# 01_-_PWR_0V9_PWR_SEQ.net
KiCad netlist of a schematic drawn in Altium Designer
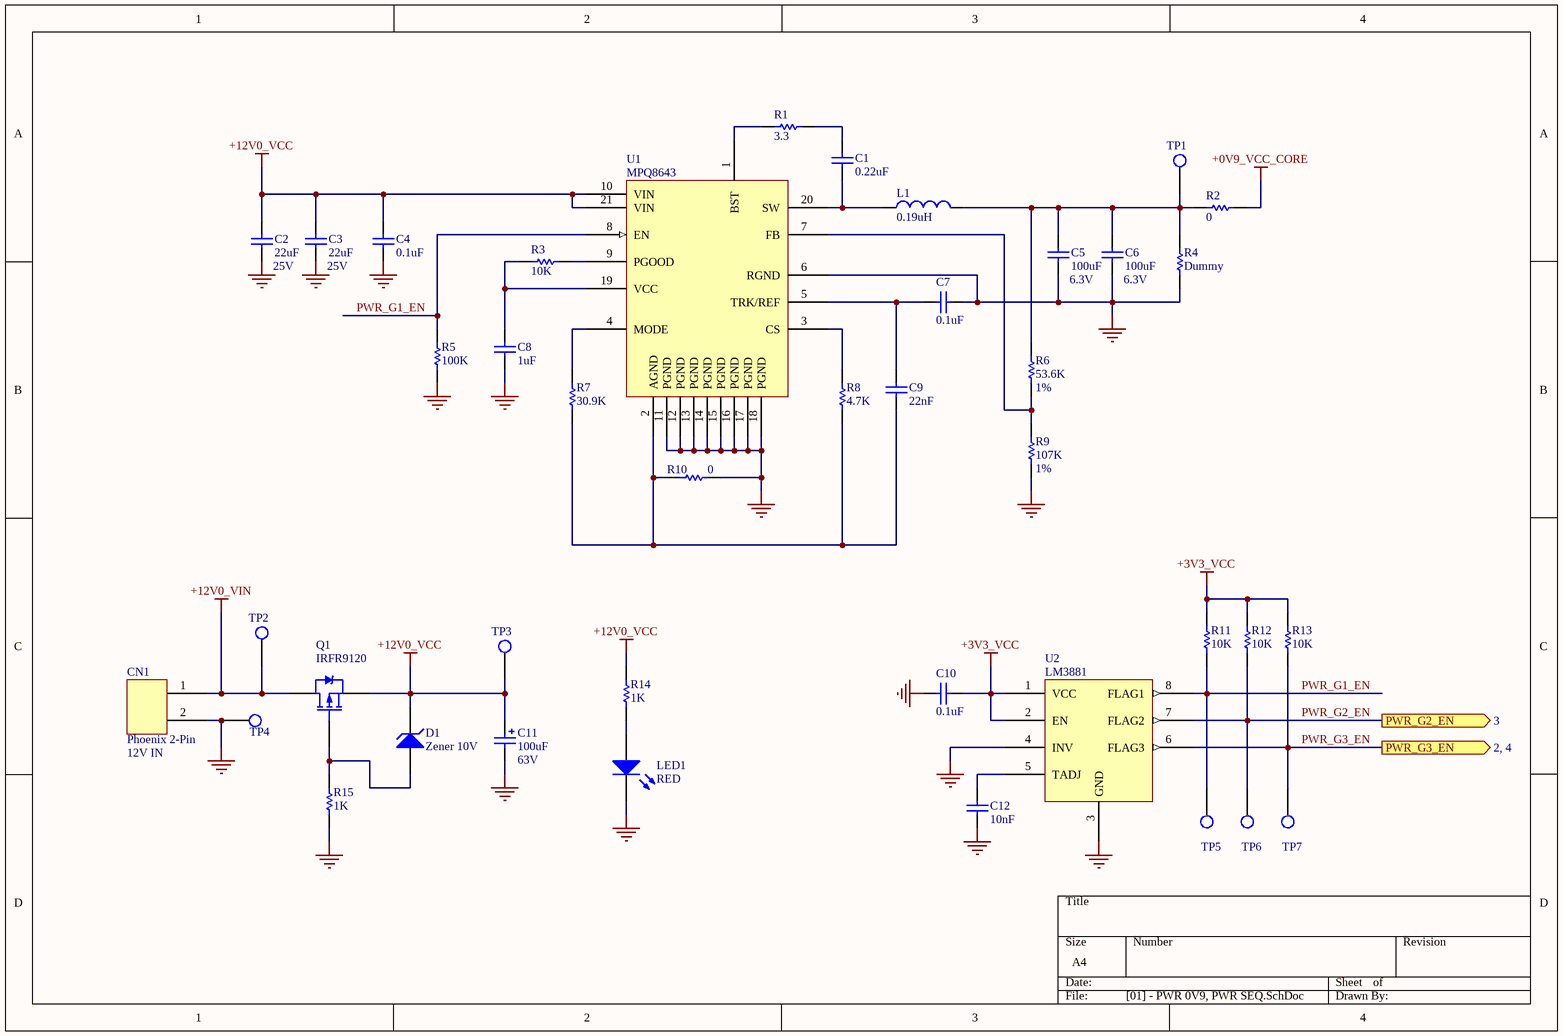
[diagram p0: [01] - PWR 0V9, PWR SEQ.SchDoc]

(export (version "E")
  (design (tool "Eeschema 10.0.6"))
  (components
    (comp (ref "C1")
      (value "0.22uF")
      (footprint "0402_C")
      (description "Non-Pol SMD Capacitor")
      (libsource (lib "Passive Components") (part "Cap SMD"))
    )
    (comp (ref "C2")
      (value "22uF")
      (footprint "1210_C")
      (description "Non-Pol SMD Capacitor")
      (fields (field (name "RATED_VOLTAGE") "25V") (field (name "MANUFACTURER PART NUM") "GRM32ER71E226KE15"))
      (libsource (lib "Passive Components") (part "Cap SMD"))
    )
    (comp (ref "C3")
      (value "22uF")
      (footprint "1210_C")
      (description "Non-Pol SMD Capacitor")
      (fields (field (name "RATED_VOLTAGE") "25V") (field (name "MANUFACTURER PART NUM") "GRM32ER71E226KE15"))
      (libsource (lib "Passive Components") (part "Cap SMD"))
    )
    (comp (ref "C4")
      (value "0.1uF")
      (footprint "0402_C")
      (description "Non-Pol SMD Capacitor")
      (libsource (lib "Passive Components") (part "Cap SMD"))
    )
    (comp (ref "C5")
      (value "100uF")
      (footprint "1210_C")
      (description "Non-Pol SMD Capacitor")
      (fields
        (field (name "RATED_VOLTAGE") "6.3V")
        (field (name "MANUFACTURER PART NUM") "GRM32EC70J107ME15")
      )
      (libsource (lib "Passive Components") (part "Cap SMD"))
    )
    (comp (ref "C6")
      (value "100uF")
      (footprint "1210_C")
      (description "Non-Pol SMD Capacitor")
      (fields
        (field (name "RATED_VOLTAGE") "6.3V")
        (field (name "MANUFACTURER PART NUM") "GRM32EC70J107ME15")
      )
      (libsource (lib "Passive Components") (part "Cap SMD"))
    )
    (comp (ref "C7")
      (value "0.1uF")
      (footprint "0402_C")
      (description "Non-Pol SMD Capacitor")
      (libsource (lib "Passive Components") (part "Cap SMD"))
    )
    (comp (ref "C8")
      (value "1uF")
      (footprint "0402_C")
      (description "Non-Pol SMD Capacitor")
      (libsource (lib "Passive Components") (part "Cap SMD"))
    )
    (comp (ref "C9")
      (value "22nF")
      (footprint "0402_C")
      (description "Non-Pol SMD Capacitor")
      (libsource (lib "Passive Components") (part "Cap SMD"))
    )
    (comp (ref "C10")
      (value "0.1uF")
      (footprint "0402_C")
      (description "Non-Pol SMD Capacitor")
      (libsource (lib "Passive Components") (part "Cap SMD"))
    )
    (comp (ref "C11")
      (value "100uF")
      (footprint "G_PANASONIC")
      (description "Aluminium Electrolytic Capacitor")
      (fields (field (name "RATED_VOLTAGE") "63V") (field (name "MANUFACTURER PART NUM") "EEE-TG1J101UP"))
      (libsource (lib "Passive Components") (part "Cap Aluminium Electrolytic"))
    )
    (comp (ref "C12")
      (value "10nF")
      (footprint "0402_C")
      (description "Non-Pol SMD Capacitor")
      (libsource (lib "Passive Components") (part "Cap SMD"))
    )
    (comp (ref "CN1")
      (value "Phoenix 2-Pin")
      (footprint "PHOENIX_2PIN_RIGHT_200mil")
      (description "2-Pin Phoenix Terminal")
      (libsource (lib "Connectors") (part "Phoenix 2 pin"))
    )
    (comp (ref "D1")
      (value "Zener 10V")
      (footprint "SOD-123")
      (description "Zener Diode")
      (fields (field (name "MANUFACTURER PART NUM") "BZT52C10-7-F"))
      (libsource (lib "Common Components") (part "Diode Zener"))
    )
    (comp (ref "L1")
      (value "0.19uH")
      (footprint "IHLP-4040")
      (description "Inductor SMD")
      (fields (field (name "MANUFACTURER PART NUM") "IHLP4040DZERR19M11"))
      (libsource (lib "Passive Components") (part "Inductor"))
    )
    (comp (ref "LED1")
      (value "RED")
      (footprint "LED_0805")
      (description "Typical LED")
      (libsource (lib "Common Components") (part "LED"))
    )
    (comp (ref "Q1")
      (value "IRFR9120")
      (footprint "TO-252")
      (description "P-Channel Mosfet")
      (fields (field (name "MANUFACTURER PART NUM") "IRFR9120PBF"))
      (libsource (lib "Common Components") (part "MOSFET P-CH"))
    )
    (comp (ref "R1")
      (value "3.3")
      (footprint "0402_R")
      (description "SMD Resistor")
      (fields (field (name "TOLERANCE") "5%"))
      (libsource (lib "Passive Components") (part "Res SMD"))
    )
    (comp (ref "R2")
      (value "0")
      (footprint "1210_R")
      (description "SMD Resistor")
      (fields (field (name "TOLERANCE") "5%"))
      (libsource (lib "Passive Components") (part "Res SMD"))
    )
    (comp (ref "R3")
      (value "10K")
      (footprint "0402_R")
      (description "SMD Resistor")
      (fields (field (name "TOLERANCE") "5%"))
      (libsource (lib "Passive Components") (part "Res SMD"))
    )
    (comp (ref "R4")
      (value "Dummy")
      (footprint "1210_R")
      (description "SMD Resistor")
      (fields (field (name "TOLERANCE") "5%"))
      (libsource (lib "Passive Components") (part "Res SMD"))
    )
    (comp (ref "R5")
      (value "100K")
      (footprint "0402_R")
      (description "SMD Resistor")
      (fields (field (name "TOLERANCE") "5%"))
      (libsource (lib "Passive Components") (part "Res SMD"))
    )
    (comp (ref "R6")
      (value "53.6K")
      (footprint "0402_R")
      (description "SMD Resistor")
      (fields (field (name "TOLERANCE") "1%"))
      (libsource (lib "Passive Components") (part "Res SMD"))
    )
    (comp (ref "R7")
      (value "30.9K")
      (footprint "0402_R")
      (description "SMD Resistor")
      (fields (field (name "TOLERANCE") "5%"))
      (libsource (lib "Passive Components") (part "Res SMD"))
    )
    (comp (ref "R8")
      (value "4.7K")
      (footprint "0402_R")
      (description "SMD Resistor")
      (fields (field (name "TOLERANCE") "5%"))
      (libsource (lib "Passive Components") (part "Res SMD"))
    )
    (comp (ref "R9")
      (value "107K")
      (footprint "0402_R")
      (description "SMD Resistor")
      (fields (field (name "TOLERANCE") "1%"))
      (libsource (lib "Passive Components") (part "Res SMD"))
    )
    (comp (ref "R10")
      (value "0")
      (footprint "0402_R")
      (description "SMD Resistor")
      (fields (field (name "TOLERANCE") "5%"))
      (libsource (lib "Passive Components") (part "Res SMD"))
    )
    (comp (ref "R11")
      (value "10K")
      (footprint "0402_R")
      (description "SMD Resistor")
      (fields (field (name "TOLERANCE") "5%"))
      (libsource (lib "Passive Components") (part "Res SMD"))
    )
    (comp (ref "R12")
      (value "10K")
      (footprint "0402_R")
      (description "SMD Resistor")
      (fields (field (name "TOLERANCE") "5%"))
      (libsource (lib "Passive Components") (part "Res SMD"))
    )
    (comp (ref "R13")
      (value "10K")
      (footprint "0402_R")
      (description "SMD Resistor")
      (fields (field (name "TOLERANCE") "5%"))
      (libsource (lib "Passive Components") (part "Res SMD"))
    )
    (comp (ref "R14")
      (value "1K")
      (footprint "0805_R")
      (description "SMD Resistor")
      (fields (field (name "TOLERANCE") "5%"))
      (libsource (lib "Passive Components") (part "Res SMD"))
    )
    (comp (ref "R15")
      (value "1K")
      (footprint "0805_R")
      (description "SMD Resistor")
      (fields (field (name "TOLERANCE") "5%"))
      (libsource (lib "Passive Components") (part "Res SMD"))
    )
    (comp (ref "TP1")
      (value "Test Point")
      (footprint "PIN_1.5mm")
      (description "Test Point Footprint")
      (libsource (lib "Passive Components") (part "Test Point"))
    )
    (comp (ref "TP2")
      (value "Test Point")
      (footprint "PIN_1.5mm")
      (description "Test Point Footprint")
      (libsource (lib "Passive Components") (part "Test Point"))
    )
    (comp (ref "TP3")
      (value "Test Point")
      (footprint "PIN_1.5mm")
      (description "Test Point Footprint")
      (libsource (lib "Passive Components") (part "Test Point"))
    )
    (comp (ref "TP4")
      (value "Test Point")
      (footprint "PIN_1.5mm")
      (description "Test Point Footprint")
      (libsource (lib "Passive Components") (part "Test Point"))
    )
    (comp (ref "TP5")
      (value "Test Point")
      (footprint "PIN_1mm")
      (description "Test Point Footprint")
      (libsource (lib "Passive Components") (part "Test Point"))
    )
    (comp (ref "TP6")
      (value "Test Point")
      (footprint "PIN_1mm")
      (description "Test Point Footprint")
      (libsource (lib "Passive Components") (part "Test Point"))
    )
    (comp (ref "TP7")
      (value "Test Point")
      (footprint "PIN_1mm")
      (description "Test Point Footprint")
      (libsource (lib "Passive Components") (part "Test Point"))
    )
    (comp (ref "U1")
      (value "MPQ8643")
      (description "16V, 20A, Configurable-Frequency, Synchronous Step-Down Converter")
      (fields (field (name "MANUFACTURER PART NUM") "MPQ8643GLE-P"))
      (libsource (lib "Project_schlib") (part "MPQ8643"))
    )
    (comp (ref "U2")
      (value "LM3881")
      (description "Simple Power Sequencer With Adjustable Timing")
      (libsource (lib "Project_schlib") (part "LM3881"))
    )
  )
  (nets
    (net (code "1") (name "+0V9_VCC_CORE") (class "Default")
      (node (ref "R2") (pin "2") (pinfunction "2_2") (pintype "passive"))
    )
    (net (code "2") (name "+3V3_VCC") (class "Default")
      (node (ref "C10") (pin "1") (pinfunction "1_1") (pintype "passive"))
      (node (ref "R11") (pin "2") (pinfunction "2_2") (pintype "passive"))
      (node (ref "R12") (pin "2") (pinfunction "2_2") (pintype "passive"))
      (node (ref "R13") (pin "2") (pinfunction "2_2") (pintype "passive"))
      (node (ref "U2") (pin "1") (pinfunction "VCC_1") (pintype "power_in"))
      (node (ref "U2") (pin "2") (pinfunction "EN_2") (pintype "passive"))
    )
    (net (code "3") (name "+12V0_VCC") (class "Default")
      (node (ref "C11") (pin "1") (pinfunction "1_1") (pintype "passive"))
      (node (ref "C2") (pin "2") (pinfunction "2_2") (pintype "passive"))
      (node (ref "C3") (pin "2") (pinfunction "2_2") (pintype "passive"))
      (node (ref "C4") (pin "2") (pinfunction "2_2") (pintype "passive"))
      (node (ref "D1") (pin "2") (pinfunction "K_2") (pintype "passive"))
      (node (ref "Q1") (pin "2") (pinfunction "S_2") (pintype "passive"))
      (node (ref "R14") (pin "2") (pinfunction "2_2") (pintype "passive"))
      (node (ref "TP3") (pin "1") (pinfunction "1_1") (pintype "passive"))
      (node (ref "U1") (pin "10") (pinfunction "VIN_10") (pintype "power_in"))
      (node (ref "U1") (pin "21") (pinfunction "VIN_21") (pintype "power_in"))
    )
    (net (code "4") (name "+12V0_VIN") (class "Default")
      (node (ref "CN1") (pin "1") (pinfunction "1_1") (pintype "passive"))
      (node (ref "Q1") (pin "3") (pinfunction "D_3") (pintype "passive"))
      (node (ref "TP2") (pin "1") (pinfunction "1_1") (pintype "passive"))
    )
    (net (code "5") (name "/PWR_G1_EN") (class "Default")
      (node (ref "R11") (pin "1") (pinfunction "1_1") (pintype "passive"))
      (node (ref "R5") (pin "1") (pinfunction "1_1") (pintype "passive"))
      (node (ref "TP5") (pin "1") (pinfunction "1_1") (pintype "passive"))
      (node (ref "U1") (pin "8") (pinfunction "EN_8") (pintype "input"))
      (node (ref "U2") (pin "8") (pinfunction "FLAG1_8") (pintype "output"))
    )
    (net (code "6") (name "/PWR_G2_EN") (class "Default")
      (node (ref "R12") (pin "1") (pinfunction "1_1") (pintype "passive"))
      (node (ref "TP6") (pin "1") (pinfunction "1_1") (pintype "passive"))
      (node (ref "U2") (pin "7") (pinfunction "FLAG2_7") (pintype "output"))
    )
    (net (code "7") (name "/PWR_G3_EN") (class "Default")
      (node (ref "R13") (pin "1") (pinfunction "1_1") (pintype "passive"))
      (node (ref "TP7") (pin "1") (pinfunction "1_1") (pintype "passive"))
      (node (ref "U2") (pin "6") (pinfunction "FLAG3_6") (pintype "output"))
    )
    (net (code "8") (name "GND") (class "Default")
      (node (ref "C10") (pin "2") (pinfunction "2_2") (pintype "passive"))
      (node (ref "C11") (pin "2") (pinfunction "2_2") (pintype "passive"))
      (node (ref "C12") (pin "2") (pinfunction "2_2") (pintype "passive"))
      (node (ref "C2") (pin "1") (pinfunction "1_1") (pintype "passive"))
      (node (ref "C3") (pin "1") (pinfunction "1_1") (pintype "passive"))
      (node (ref "C4") (pin "1") (pinfunction "1_1") (pintype "passive"))
      (node (ref "C5") (pin "1") (pinfunction "1_1") (pintype "passive"))
      (node (ref "C6") (pin "1") (pinfunction "1_1") (pintype "passive"))
      (node (ref "C7") (pin "1") (pinfunction "1_1") (pintype "passive"))
      (node (ref "C8") (pin "1") (pinfunction "1_1") (pintype "passive"))
      (node (ref "CN1") (pin "2") (pinfunction "2_2") (pintype "passive"))
      (node (ref "LED1") (pin "2") (pinfunction "K_2") (pintype "passive"))
      (node (ref "R10") (pin "2") (pinfunction "2_2") (pintype "passive"))
      (node (ref "R15") (pin "1") (pinfunction "1_1") (pintype "passive"))
      (node (ref "R4") (pin "1") (pinfunction "1_1") (pintype "passive"))
      (node (ref "R5") (pin "2") (pinfunction "2_2") (pintype "passive"))
      (node (ref "R9") (pin "1") (pinfunction "1_1") (pintype "passive"))
      (node (ref "TP4") (pin "1") (pinfunction "1_1") (pintype "passive"))
      (node (ref "U1") (pin "11") (pinfunction "PGND_11") (pintype "power_in"))
      (node (ref "U1") (pin "12") (pinfunction "PGND_12") (pintype "power_in"))
      (node (ref "U1") (pin "13") (pinfunction "PGND_13") (pintype "power_in"))
      (node (ref "U1") (pin "14") (pinfunction "PGND_14") (pintype "power_in"))
      (node (ref "U1") (pin "15") (pinfunction "PGND_15") (pintype "power_in"))
      (node (ref "U1") (pin "16") (pinfunction "PGND_16") (pintype "power_in"))
      (node (ref "U1") (pin "17") (pinfunction "PGND_17") (pintype "power_in"))
      (node (ref "U1") (pin "18") (pinfunction "PGND_18") (pintype "power_in"))
      (node (ref "U1") (pin "6") (pinfunction "RGND_6") (pintype "power_in"))
      (node (ref "U2") (pin "3") (pinfunction "GND_3") (pintype "power_in"))
      (node (ref "U2") (pin "4") (pinfunction "INV_4") (pintype "passive"))
    )
    (net (code "9") (name "Net-(C1-Pad2)") (class "Default")
      (node (ref "C1") (pin "2") (pinfunction "2_2") (pintype "passive"))
      (node (ref "R1") (pin "2") (pinfunction "2_2") (pintype "passive"))
    )
    (net (code "10") (name "Net-(C5-Pad2)") (class "Default")
      (node (ref "C5") (pin "2") (pinfunction "2_2") (pintype "passive"))
      (node (ref "C6") (pin "2") (pinfunction "2_2") (pintype "passive"))
      (node (ref "L1") (pin "2") (pinfunction "2_2") (pintype "passive"))
      (node (ref "R2") (pin "1") (pinfunction "1_1") (pintype "passive"))
      (node (ref "R4") (pin "2") (pinfunction "2_2") (pintype "passive"))
      (node (ref "R6") (pin "2") (pinfunction "2_2") (pintype "passive"))
      (node (ref "TP1") (pin "1") (pinfunction "1_1") (pintype "passive"))
    )
    (net (code "11") (name "Net-(D1-A)") (class "Default")
      (node (ref "D1") (pin "1") (pinfunction "A_1") (pintype "passive"))
      (node (ref "Q1") (pin "1") (pinfunction "G_1") (pintype "passive"))
      (node (ref "R15") (pin "2") (pinfunction "2_2") (pintype "passive"))
    )
    (net (code "12") (name "Net-(LED1-A)") (class "Default")
      (node (ref "LED1") (pin "1") (pinfunction "A_1") (pintype "passive"))
      (node (ref "R14") (pin "1") (pinfunction "1_1") (pintype "passive"))
    )
    (net (code "13") (name "Net-(U1-AGND)") (class "Default")
      (node (ref "C9") (pin "1") (pinfunction "1_1") (pintype "passive"))
      (node (ref "R10") (pin "1") (pinfunction "1_1") (pintype "passive"))
      (node (ref "R7") (pin "1") (pinfunction "1_1") (pintype "passive"))
      (node (ref "R8") (pin "1") (pinfunction "1_1") (pintype "passive"))
      (node (ref "U1") (pin "2") (pinfunction "AGND_2") (pintype "power_in"))
    )
    (net (code "14") (name "Net-(U1-BST)") (class "Default")
      (node (ref "R1") (pin "1") (pinfunction "1_1") (pintype "passive"))
      (node (ref "U1") (pin "1") (pinfunction "BST_1") (pintype "power_in"))
    )
    (net (code "15") (name "Net-(U1-CS)") (class "Default")
      (node (ref "R8") (pin "2") (pinfunction "2_2") (pintype "passive"))
      (node (ref "U1") (pin "3") (pinfunction "CS_3") (pintype "power_in"))
    )
    (net (code "16") (name "Net-(U1-FB)") (class "Default")
      (node (ref "R6") (pin "1") (pinfunction "1_1") (pintype "passive"))
      (node (ref "R9") (pin "2") (pinfunction "2_2") (pintype "passive"))
      (node (ref "U1") (pin "7") (pinfunction "FB_7") (pintype "power_in"))
    )
    (net (code "17") (name "Net-(U1-MODE)") (class "Default")
      (node (ref "R7") (pin "2") (pinfunction "2_2") (pintype "passive"))
      (node (ref "U1") (pin "4") (pinfunction "MODE_4") (pintype "passive"))
    )
    (net (code "18") (name "Net-(U1-PGOOD)") (class "Default")
      (node (ref "R3") (pin "1") (pinfunction "1_1") (pintype "passive"))
      (node (ref "U1") (pin "9") (pinfunction "PGOOD_9") (pintype "power_in"))
    )
    (net (code "19") (name "Net-(U1-SW)") (class "Default")
      (node (ref "C1") (pin "1") (pinfunction "1_1") (pintype "passive"))
      (node (ref "L1") (pin "1") (pinfunction "1_1") (pintype "passive"))
      (node (ref "U1") (pin "20") (pinfunction "SW_20") (pintype "power_in"))
    )
    (net (code "20") (name "Net-(U1-TRK{slash}REF)") (class "Default")
      (node (ref "C7") (pin "2") (pinfunction "2_2") (pintype "passive"))
      (node (ref "C9") (pin "2") (pinfunction "2_2") (pintype "passive"))
      (node (ref "U1") (pin "5") (pinfunction "TRK/REF_5") (pintype "power_in"))
    )
    (net (code "21") (name "Net-(U1-VCC)") (class "Default")
      (node (ref "C8") (pin "2") (pinfunction "2_2") (pintype "passive"))
      (node (ref "R3") (pin "2") (pinfunction "2_2") (pintype "passive"))
      (node (ref "U1") (pin "19") (pinfunction "VCC_19") (pintype "power_in"))
    )
    (net (code "22") (name "Net-(U2-TADJ)") (class "Default")
      (node (ref "C12") (pin "1") (pinfunction "1_1") (pintype "passive"))
      (node (ref "U2") (pin "5") (pinfunction "TADJ_5") (pintype "passive"))
    )
  )
)
